# 4_memory.net
KiCad netlist of a schematic drawn in Altium Designer
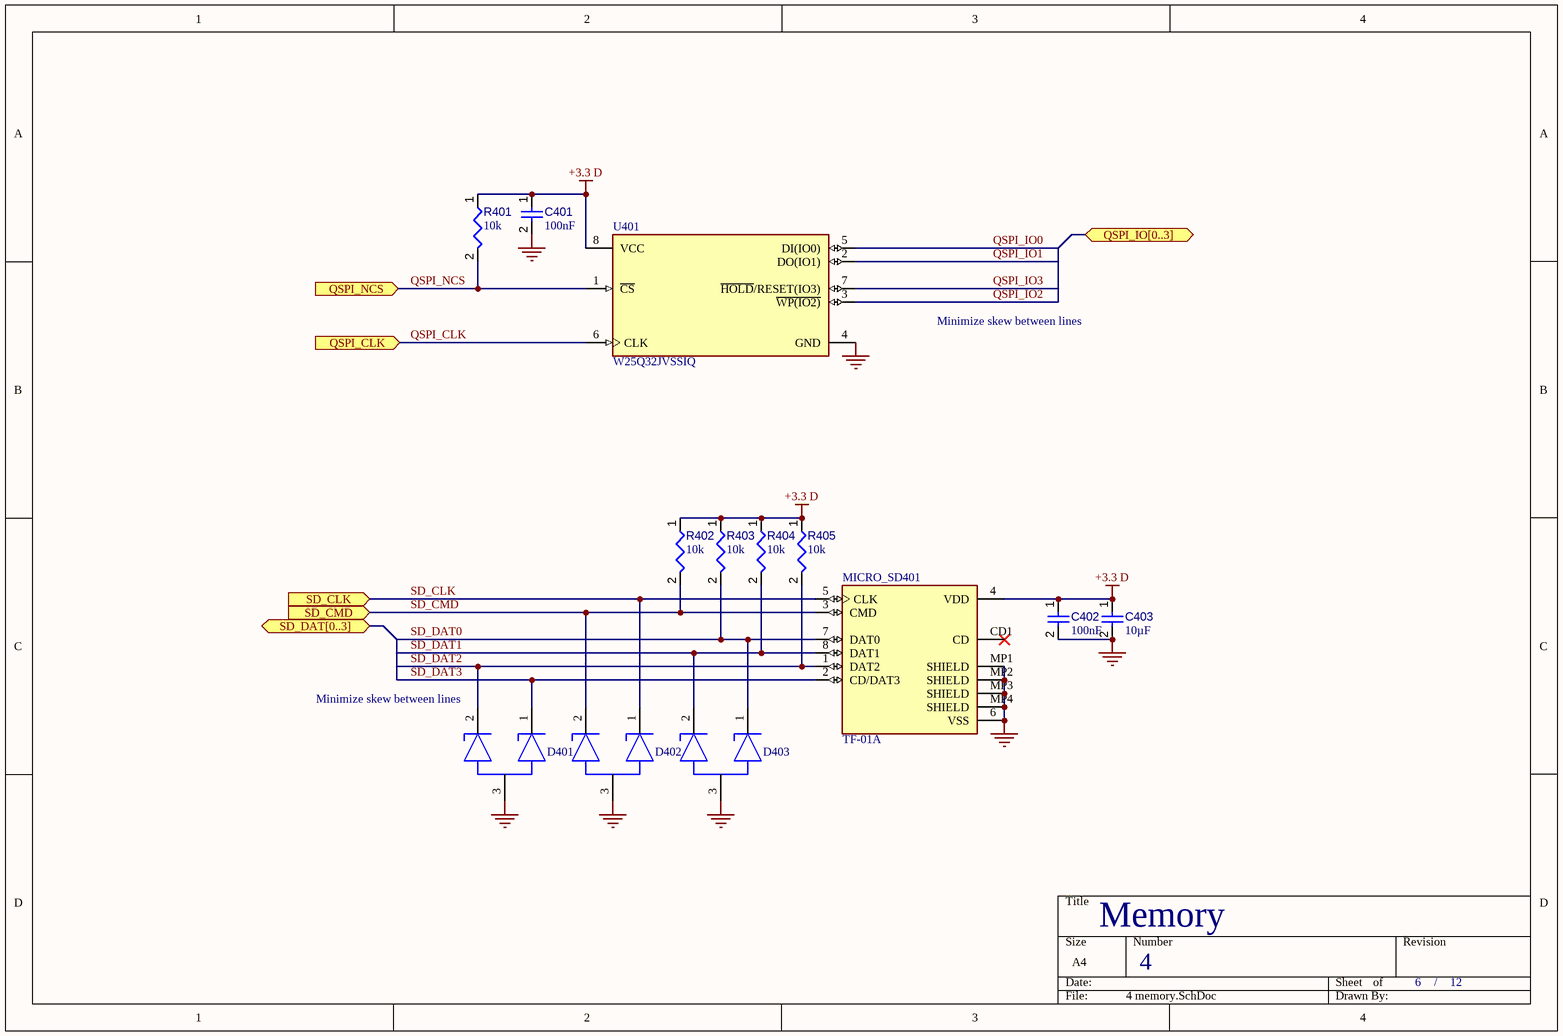
[diagram p0: 4 memory.SchDoc]

(export (version "E")
  (design (tool "Eeschema 10.0.6"))
  (components
    (comp (ref "C401")
      (value "100nF")
      (footprint "CAPC0402(1005)60_L")
      (description "Chip Capacitor, 100nF +/-20%, 25V, 0402, Thickness 0.6 mm")
      (fields (field (name "TOLERANCE") "10%") (field (name "Comment") "Capacitor 100nF +/-20% 25V 0402"))
      (libsource (lib "UBC Uncrewed Aircraft Systems") (part "CAP-NP-2"))
    )
    (comp (ref "C402")
      (value "100nF")
      (footprint "CAPC0402(1005)60_L")
      (description "Chip Capacitor, 100nF +/-20%, 25V, 0402, Thickness 0.6 mm")
      (fields (field (name "TOLERANCE") "10%") (field (name "Comment") "Capacitor 100nF +/-20% 25V 0402"))
      (libsource (lib "UBC Uncrewed Aircraft Systems") (part "CAP-NP-2"))
    )
    (comp (ref "C403")
      (value "10µF")
      (footprint "CAPC0603(1608)100_L")
      (description "Chip Capacitor, 10µF +/-20%, 10V, 0603, Thickness 1 mm")
      (fields (field (name "TOLERANCE") "10%") (field (name "Comment") "Capacitor 10µF +/-20% 10V 0603"))
      (libsource (lib "UBC Uncrewed Aircraft Systems") (part "CAP-NP-2"))
    )
    (comp (ref "D401")
      (value "PESD3V3S2UT,215")
      (footprint "FP-SOT23-IPC_A")
      (description "TVS DIODE 3.3VWM 20VC TO236AB")
      (libsource (lib "Altium Content Vault") (part "05bab3e457e9f60b0f1ca7a96343362"))
    )
    (comp (ref "D402")
      (value "PESD3V3S2UT,215")
      (footprint "FP-SOT23-IPC_A")
      (description "TVS DIODE 3.3VWM 20VC TO236AB")
      (libsource (lib "Altium Content Vault") (part "05bab3e457e9f60b0f1ca7a96343362"))
    )
    (comp (ref "D403")
      (value "PESD3V3S2UT,215")
      (footprint "FP-SOT23-IPC_A")
      (description "TVS DIODE 3.3VWM 20VC TO236AB")
      (libsource (lib "Altium Content Vault") (part "05bab3e457e9f60b0f1ca7a96343362"))
    )
    (comp (ref "MICRO_SD401")
      (value "TF-01A")
      (footprint "TF-01A")
      (description "Standard Card Edge Connectors")
      (fields (field (name "MF") "HRO Electronics Co., Ltd."))
      (libsource (lib "TF-01A") (part "TF-01A"))
    )
    (comp (ref "R401")
      (value "10k")
      (footprint "RESC0402(1005)_L")
      (description "Chip Resistor, 10 kOhms, +/-1 %, 63 mW, -55 to 125 degC, 0402")
      (fields (field (name "POWER") "63mW") (field (name "TOLERANCE") "1%"))
      (libsource (lib "UBC Uncrewed Aircraft Systems") (part "RES-2"))
    )
    (comp (ref "R402")
      (value "10k")
      (footprint "RESC0402(1005)_L")
      (description "Chip Resistor, 10 kOhms, +/-1 %, 63 mW, -55 to 125 degC, 0402")
      (fields (field (name "POWER") "63mW") (field (name "TOLERANCE") "1%"))
      (libsource (lib "UBC Uncrewed Aircraft Systems") (part "RES-2"))
    )
    (comp (ref "R403")
      (value "10k")
      (footprint "RESC0402(1005)_L")
      (description "Chip Resistor, 10 kOhms, +/-1 %, 63 mW, -55 to 125 degC, 0402")
      (fields (field (name "POWER") "63mW") (field (name "TOLERANCE") "1%"))
      (libsource (lib "UBC Uncrewed Aircraft Systems") (part "RES-2"))
    )
    (comp (ref "R404")
      (value "10k")
      (footprint "RESC0402(1005)_L")
      (description "Chip Resistor, 10 kOhms, +/-1 %, 63 mW, -55 to 125 degC, 0402")
      (fields (field (name "POWER") "63mW") (field (name "TOLERANCE") "1%"))
      (libsource (lib "UBC Uncrewed Aircraft Systems") (part "RES-2"))
    )
    (comp (ref "R405")
      (value "10k")
      (footprint "RESC0402(1005)_L")
      (description "Chip Resistor, 10 kOhms, +/-1 %, 63 mW, -55 to 125 degC, 0402")
      (fields (field (name "POWER") "63mW") (field (name "TOLERANCE") "1%"))
      (libsource (lib "UBC Uncrewed Aircraft Systems") (part "RES-2"))
    )
    (comp (ref "U401")
      (value "W25Q32JVSSIQ")
      (footprint "FP-SS-IPC_C")
      (description "IC FLASH 32M SPI 104MHZ 8SOIC")
      (fields
        (field (name "MANUFACTURER") "Winbond")
        (field (name "OCTOPART") "https://octopart.com/w25q32fvssig-winbond-23896462")
      )
      (libsource (lib "Altium Content Vault") (part "4804fbe011262506d6ec6a9051036b0"))
    )
  )
  (nets
    (net (code "1") (name "+3.3 D") (class "Default")
      (node (ref "C401") (pin "1") (pinfunction "1_1") (pintype "passive"))
      (node (ref "C402") (pin "1") (pinfunction "1_1") (pintype "passive"))
      (node (ref "C403") (pin "1") (pinfunction "1_1") (pintype "passive"))
      (node (ref "MICRO_SD401") (pin "4") (pinfunction "VDD_4") (pintype "power_in"))
      (node (ref "R401") (pin "1") (pinfunction "1_1") (pintype "passive"))
      (node (ref "R402") (pin "1") (pinfunction "1_1") (pintype "passive"))
      (node (ref "R403") (pin "1") (pinfunction "1_1") (pintype "passive"))
      (node (ref "R404") (pin "1") (pinfunction "1_1") (pintype "passive"))
      (node (ref "R405") (pin "1") (pinfunction "1_1") (pintype "passive"))
      (node (ref "U401") (pin "8") (pinfunction "VCC_8") (pintype "power_in"))
    )
    (net (code "2") (name "/QSPI_CLK") (class "Default")
      (node (ref "U401") (pin "6") (pinfunction "CLK_6") (pintype "input"))
    )
    (net (code "3") (name "/QSPI_IO0") (class "Default")
      (node (ref "U401") (pin "5") (pinfunction "DI(IO0)_5") (pintype "bidirectional"))
    )
    (net (code "4") (name "/QSPI_IO1") (class "Default")
      (node (ref "U401") (pin "2") (pinfunction "DO(IO1)_2") (pintype "bidirectional"))
    )
    (net (code "5") (name "/QSPI_IO2") (class "Default")
      (node (ref "U401") (pin "3") (pinfunction "~{WP(IO2)}_3") (pintype "bidirectional"))
    )
    (net (code "6") (name "/QSPI_IO3") (class "Default")
      (node (ref "U401") (pin "7") (pinfunction "~{HOLD}/RESET(IO3)_7") (pintype "bidirectional"))
    )
    (net (code "8") (name "/QSPI_NCS") (class "Default")
      (node (ref "R401") (pin "2") (pinfunction "2_2") (pintype "passive"))
      (node (ref "U401") (pin "1") (pinfunction "~{CS}_1") (pintype "input"))
    )
    (net (code "9") (name "/SD_CLK") (class "Default")
      (node (ref "D402") (pin "1") (pinfunction "1_1") (pintype "passive"))
      (node (ref "MICRO_SD401") (pin "5") (pinfunction "CLK_5") (pintype "bidirectional"))
    )
    (net (code "10") (name "/SD_CMD") (class "Default")
      (node (ref "D402") (pin "2") (pinfunction "2_2") (pintype "passive"))
      (node (ref "MICRO_SD401") (pin "3") (pinfunction "CMD_3") (pintype "bidirectional"))
      (node (ref "R402") (pin "2") (pinfunction "2_2") (pintype "passive"))
    )
    (net (code "11") (name "/SD_DAT0") (class "Default")
      (node (ref "D403") (pin "1") (pinfunction "1_1") (pintype "passive"))
      (node (ref "MICRO_SD401") (pin "7") (pinfunction "DAT0_7") (pintype "bidirectional"))
      (node (ref "R403") (pin "2") (pinfunction "2_2") (pintype "passive"))
    )
    (net (code "12") (name "/SD_DAT1") (class "Default")
      (node (ref "D403") (pin "2") (pinfunction "2_2") (pintype "passive"))
      (node (ref "MICRO_SD401") (pin "8") (pinfunction "DAT1_8") (pintype "bidirectional"))
      (node (ref "R404") (pin "2") (pinfunction "2_2") (pintype "passive"))
    )
    (net (code "13") (name "/SD_DAT2") (class "Default")
      (node (ref "D401") (pin "2") (pinfunction "2_2") (pintype "passive"))
      (node (ref "MICRO_SD401") (pin "1") (pinfunction "DAT2_1") (pintype "bidirectional"))
      (node (ref "R405") (pin "2") (pinfunction "2_2") (pintype "passive"))
    )
    (net (code "14") (name "/SD_DAT3") (class "Default")
      (node (ref "D401") (pin "1") (pinfunction "1_1") (pintype "passive"))
      (node (ref "MICRO_SD401") (pin "2") (pinfunction "CD/DAT3_2") (pintype "bidirectional"))
    )
    (net (code "16") (name "GND") (class "Default")
      (node (ref "C401") (pin "2") (pinfunction "2_2") (pintype "passive"))
      (node (ref "C402") (pin "2") (pinfunction "2_2") (pintype "passive"))
      (node (ref "C403") (pin "2") (pinfunction "2_2") (pintype "passive"))
      (node (ref "D401") (pin "3") (pinfunction "3_3") (pintype "passive"))
      (node (ref "D402") (pin "3") (pinfunction "3_3") (pintype "passive"))
      (node (ref "D403") (pin "3") (pinfunction "3_3") (pintype "passive"))
      (node (ref "MICRO_SD401") (pin "6") (pinfunction "VSS_6") (pintype "power_in"))
      (node (ref "MICRO_SD401") (pin "MP1") (pinfunction "SHIELD_MP1") (pintype "power_in"))
      (node (ref "MICRO_SD401") (pin "MP2") (pinfunction "SHIELD_MP2") (pintype "power_in"))
      (node (ref "MICRO_SD401") (pin "MP3") (pinfunction "SHIELD_MP3") (pintype "power_in"))
      (node (ref "MICRO_SD401") (pin "MP4") (pinfunction "SHIELD_MP4") (pintype "power_in"))
      (node (ref "U401") (pin "4") (pinfunction "GND_4") (pintype "power_in"))
    )
    (net (code "17") (name "unconnected-(MICRO_SD401-CD-PadCD1)") (class "Default")
      (node (ref "MICRO_SD401") (pin "CD1") (pinfunction "CD_CD1") (pintype "passive+no_connect"))
    )
  )
)
